# Eagle_Relay.net
KiCad netlist of a schematic drawn in EAGLE
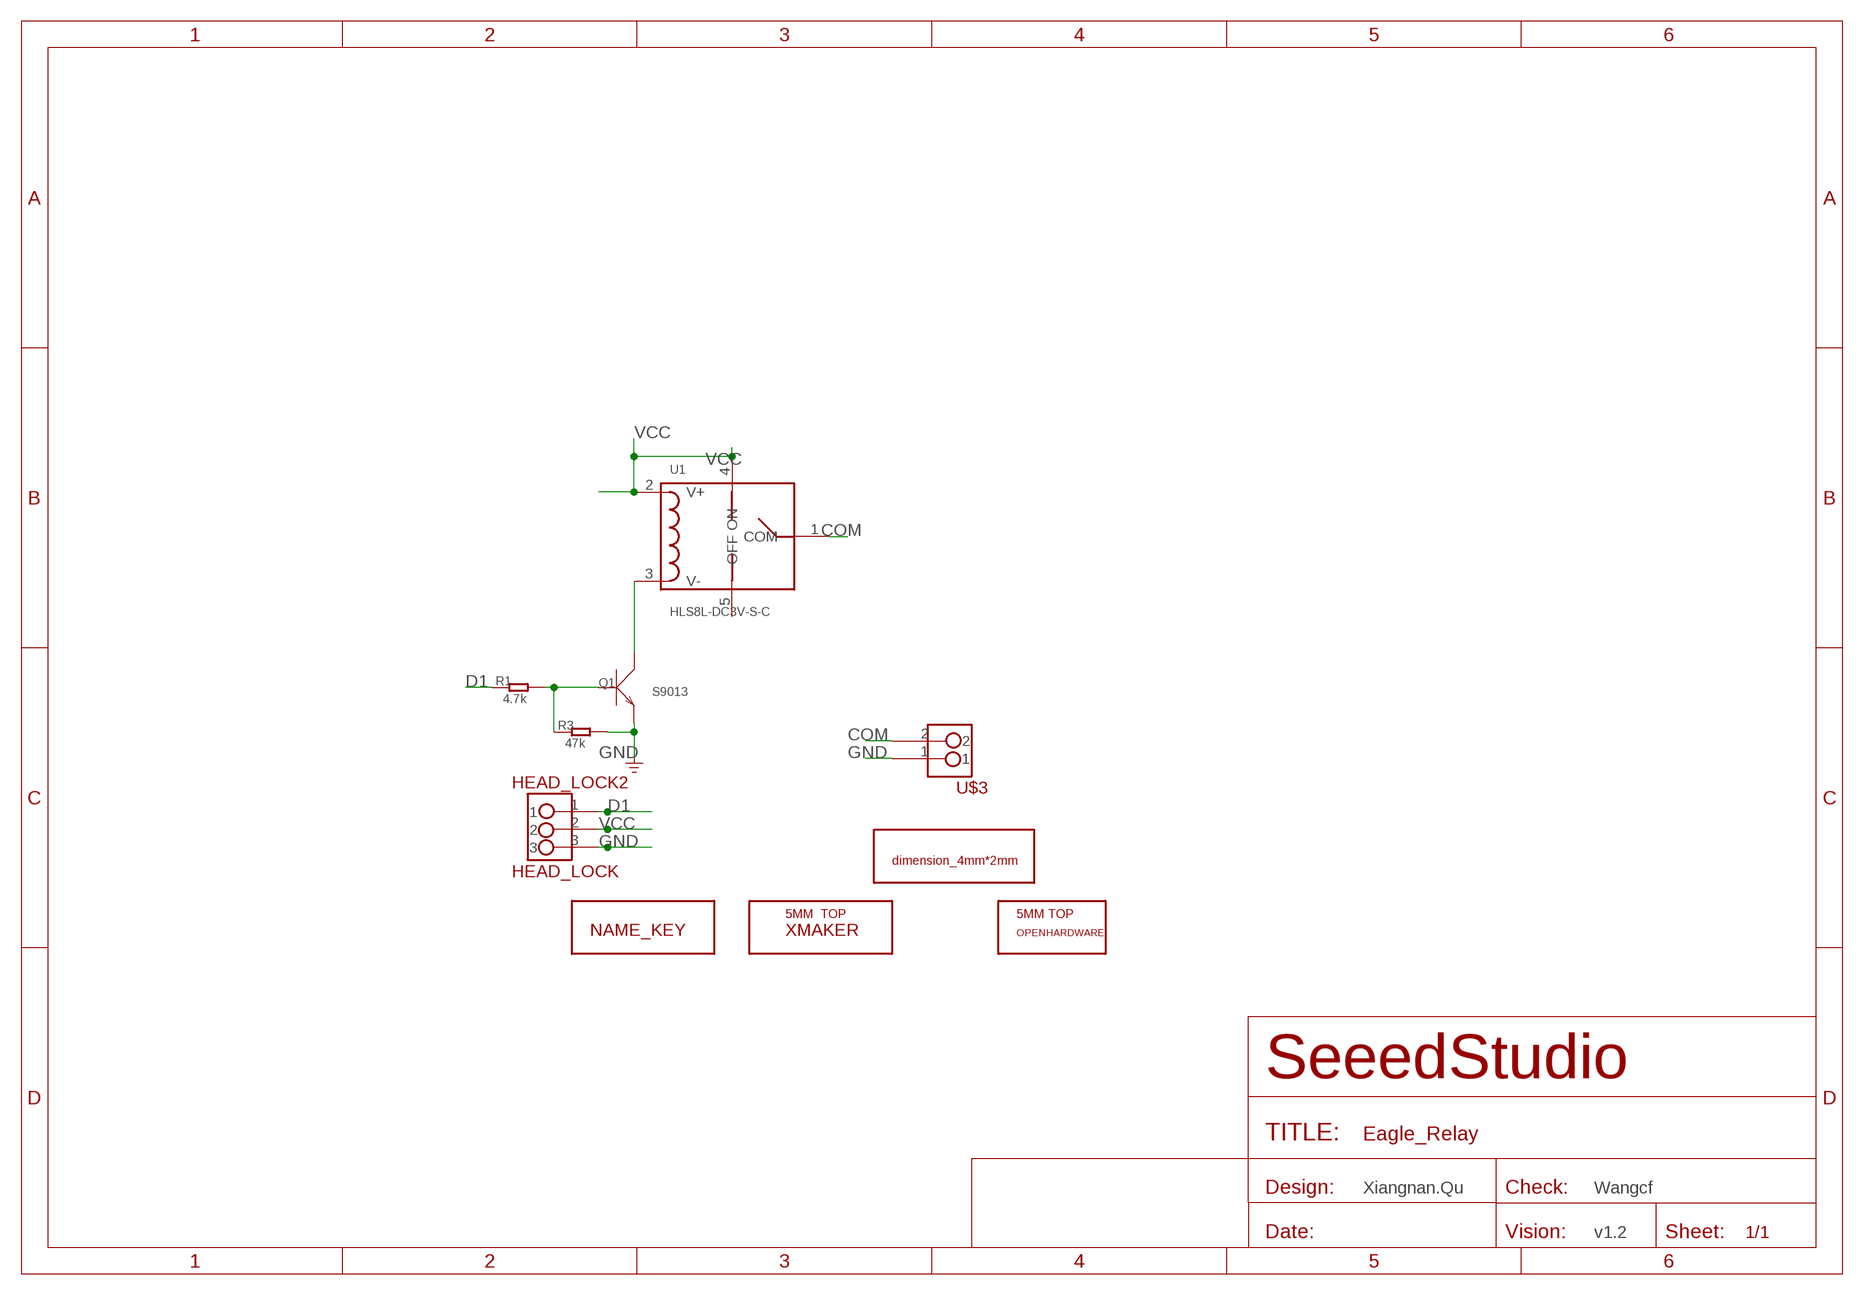
[diagram p0: schematic, sheet 1]

(export (version "E")
  (design (tool "Eeschema 10.0.6"))
  (components
    (comp (ref "HEAD_LOCK2")
      (value "HEAD_LOCK")
      (footprint "eagle-import:HEAD_LOCK")
      (libsource (lib "eagle-import") (part "HEAD_LOCK"))
    )
    (comp (ref "Q1")
      (value "S9013")
      (footprint "eagle-import:SOT23")
      (libsource (lib "eagle-import") (part "TRANSISTOR-NPN-SOT23"))
    )
    (comp (ref "R1")
      (value "4.7k")
      (footprint "eagle-import:R0603")
      (libsource (lib "eagle-import") (part "R-0603"))
    )
    (comp (ref "R3")
      (value "47k")
      (footprint "eagle-import:R0603")
      (libsource (lib "eagle-import") (part "R-0603"))
    )
    (comp (ref "U$2")
      (value "XMAKERLOGO_5MM_TOP")
      (footprint "eagle-import:XMAKERLOGO_5MM_TOP")
      (libsource (lib "eagle-import") (part "XMAKERLOGO_5MM_TOP"))
    )
    (comp (ref "U$3")
      (value "HEAD_LOCK2")
      (footprint "eagle-import:HEAD_LOCK2")
      (libsource (lib "eagle-import") (part "HEAD_LOCK2"))
    )
    (comp (ref "U$5")
      (value "NAME_RELAY")
      (footprint "eagle-import:NAME_RELAY")
      (libsource (lib "eagle-import") (part "NAME_RELAY"))
    )
    (comp (ref "U$6")
      (value "DIMENSION_4MM2MM")
      (footprint "eagle-import:DIMENSION_2MM_4MM")
      (libsource (lib "eagle-import") (part "DIMENSION_4MM2MM"))
    )
    (comp (ref "U$8")
      (value "OPENHARDWARE_5MM_TOP")
      (footprint "eagle-import:OPENSOURCE_5MM_TOP")
      (libsource (lib "eagle-import") (part "OPENHARDWARE_5MM_TOP"))
    )
    (comp (ref "U1")
      (value "HLS8L-DC3V-S-C")
      (footprint "eagle-import:RELAY")
      (libsource (lib "eagle-import") (part "RELAY"))
    )
  )
  (nets
    (net (code "1") (name "/COM") (class "Default")
      (node (ref "U$3") (pin "2") (pinfunction "2_2") (pintype "passive"))
      (node (ref "U1") (pin "1") (pinfunction "COM_1") (pintype "bidirectional"))
    )
    (net (code "2") (name "/D1") (class "Default")
      (node (ref "HEAD_LOCK2") (pin "1") (pinfunction "1_1") (pintype "passive"))
      (node (ref "R1") (pin "1") (pinfunction "1_1") (pintype "passive"))
    )
    (net (code "3") (name "/VCC") (class "Default")
      (node (ref "HEAD_LOCK2") (pin "2") (pinfunction "2_2") (pintype "passive"))
      (node (ref "U1") (pin "2") (pinfunction "V+_2") (pintype "bidirectional"))
      (node (ref "U1") (pin "4") (pinfunction "ON_4") (pintype "bidirectional"))
    )
    (net (code "4") (name "GND_POWER") (class "Default")
      (node (ref "HEAD_LOCK2") (pin "3") (pinfunction "3_3") (pintype "passive"))
      (node (ref "Q1") (pin "2") (pinfunction "E_2") (pintype "passive"))
      (node (ref "R3") (pin "2") (pinfunction "2_2") (pintype "passive"))
      (node (ref "U$3") (pin "1") (pinfunction "1_1") (pintype "passive"))
    )
    (net (code "5") (name "Net-(Q1-B)") (class "Default")
      (node (ref "Q1") (pin "1") (pinfunction "B_1") (pintype "passive"))
      (node (ref "R1") (pin "2") (pinfunction "2_2") (pintype "passive"))
      (node (ref "R3") (pin "1") (pinfunction "1_1") (pintype "passive"))
    )
    (net (code "6") (name "Net-(Q1-C)") (class "Default")
      (node (ref "Q1") (pin "3") (pinfunction "C_3") (pintype "passive"))
      (node (ref "U1") (pin "3") (pinfunction "V-_3") (pintype "bidirectional"))
    )
    (net (code "7") (name "unconnected-(U1-OFF-Pad5)") (class "Default")
      (node (ref "U1") (pin "5") (pinfunction "OFF_5") (pintype "bidirectional"))
    )
  )
)
